# 10_-_FTDI.net
KiCad netlist of a schematic drawn in Altium Designer
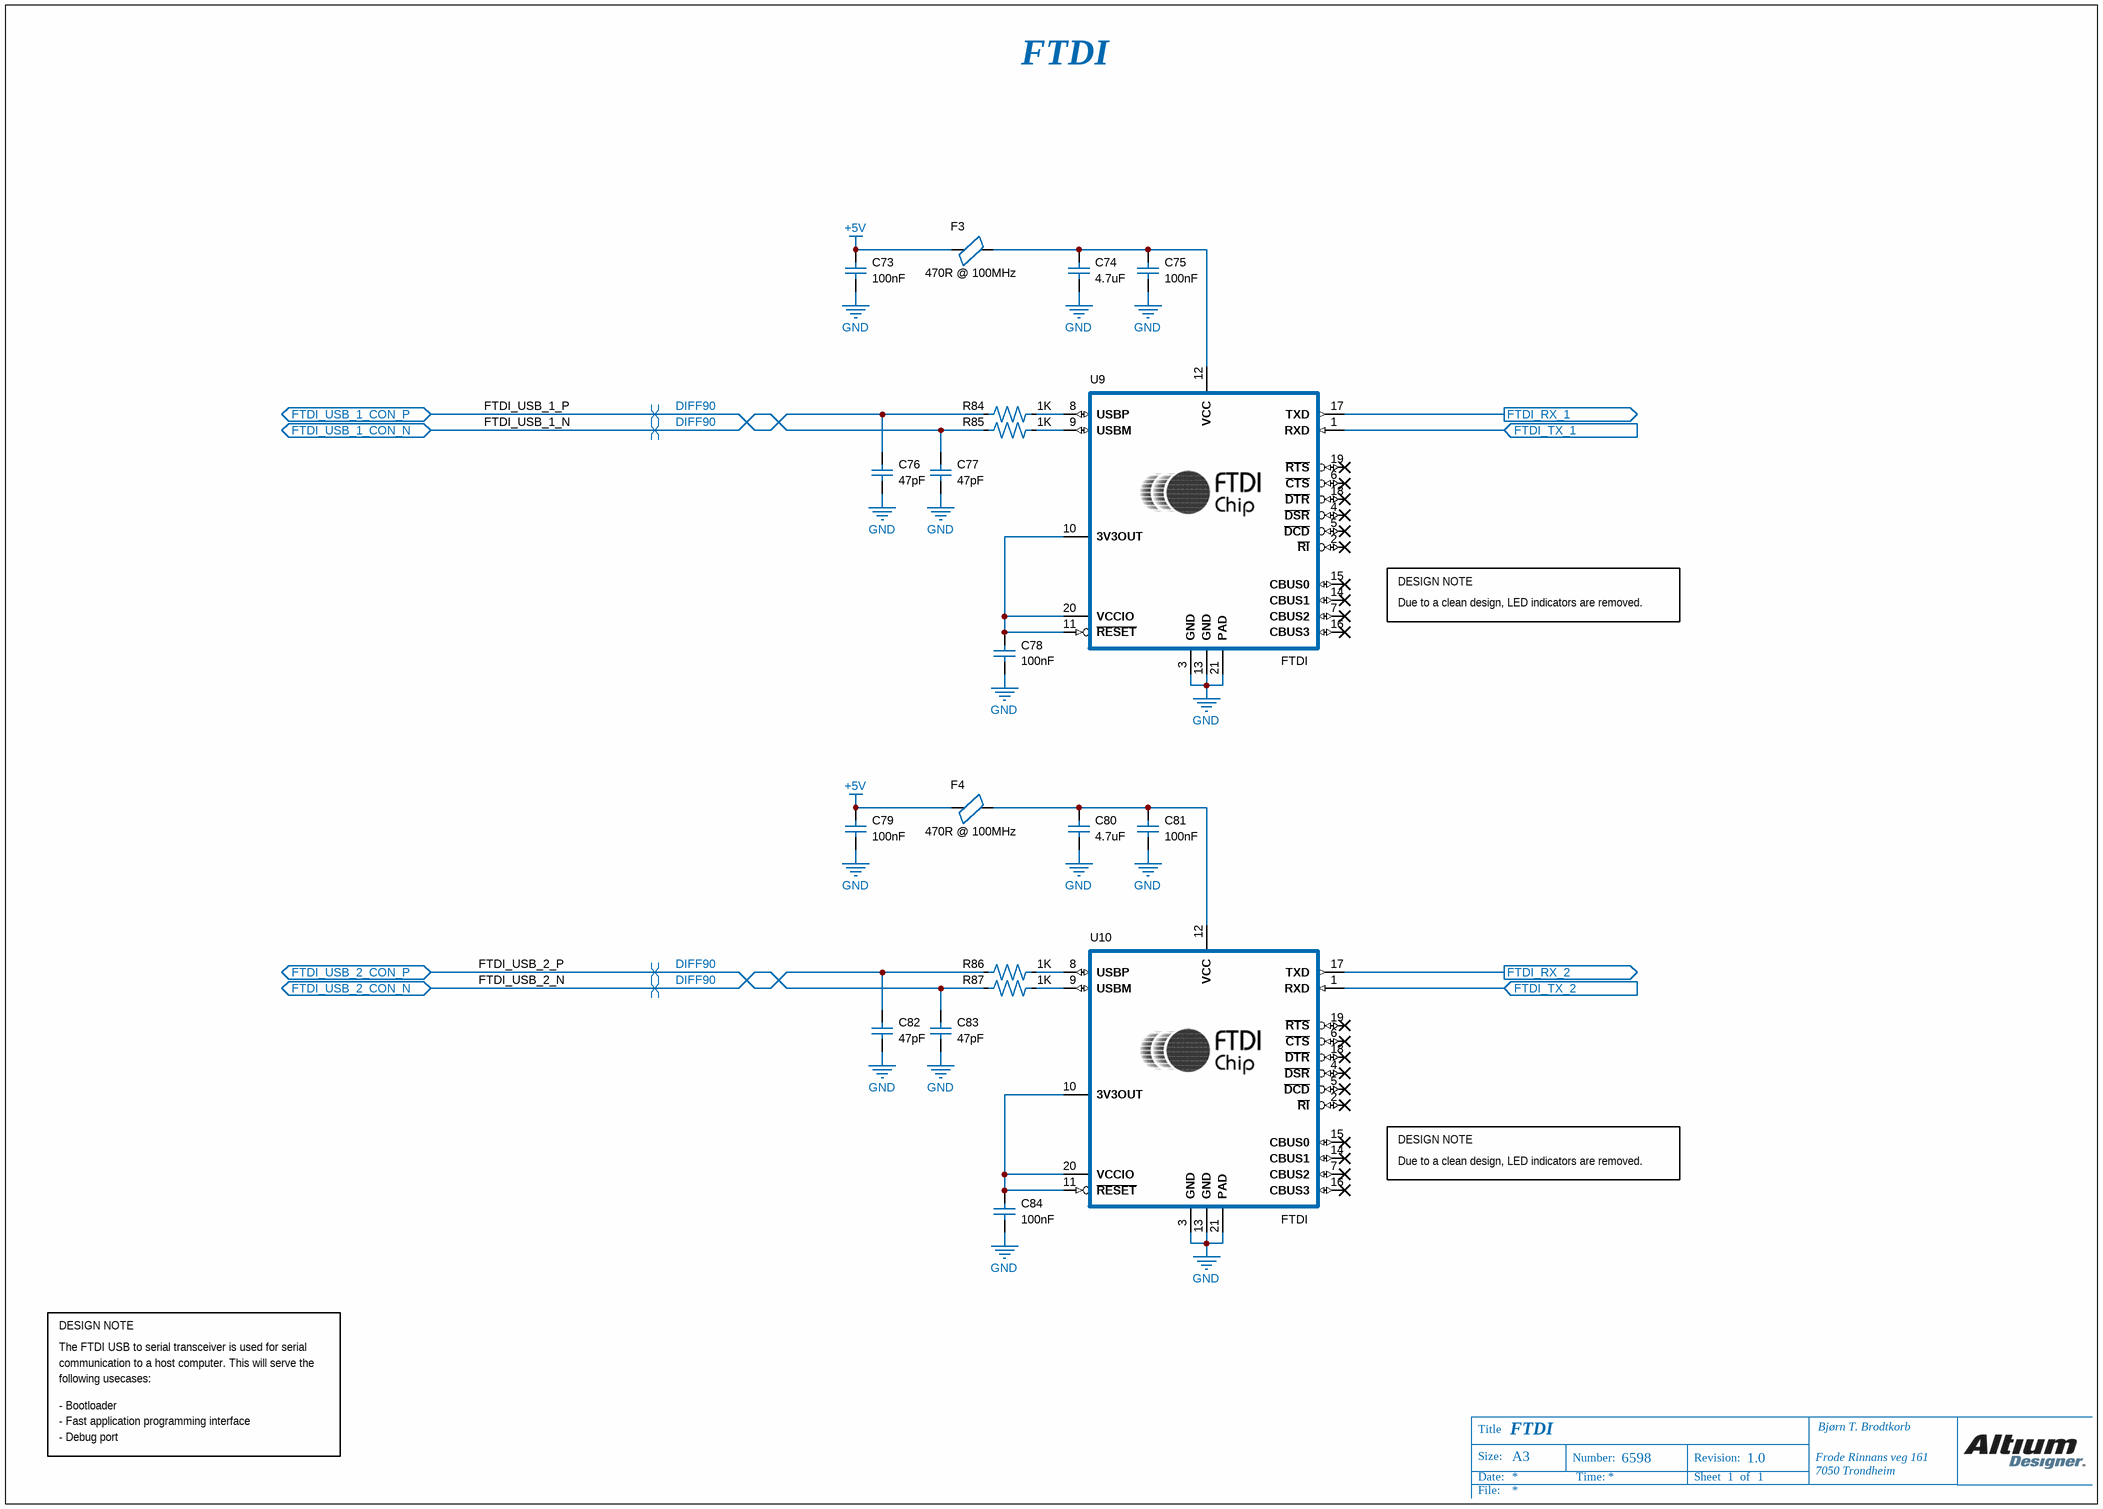
[diagram p0: [10] - FTDI.SchDoc]

(export (version "E")
  (design (tool "Eeschema 10.0.6"))
  (components
    (comp (ref "C73")
      (value "100nF")
      (footprint "C0402")
      (description "C0402")
      (fields (field (name "Comment") "04023C103KAT2A"))
      (libsource (lib "Passive components") (part "04023C103KAT2A"))
    )
    (comp (ref "C74")
      (value "4.7uF")
      (footprint "C0603")
      (description "C0603")
      (fields (field (name "Comment") "02016D104KAT2A"))
      (libsource (lib "Passive components") (part "02016D104KAT2A"))
    )
    (comp (ref "C75")
      (value "100nF")
      (footprint "C0402")
      (description "C0402")
      (fields (field (name "Comment") "04023C103KAT2A"))
      (libsource (lib "Passive components") (part "04023C103KAT2A"))
    )
    (comp (ref "C76")
      (value "47pF")
      (footprint "C0402")
      (description "C0402")
      (fields (field (name "Comment") "04023C103KAT2A"))
      (libsource (lib "Passive components") (part "04023C103KAT2A"))
    )
    (comp (ref "C77")
      (value "47pF")
      (footprint "C0402")
      (description "C0402")
      (fields (field (name "Comment") "04023C103KAT2A"))
      (libsource (lib "Passive components") (part "04023C103KAT2A"))
    )
    (comp (ref "C78")
      (value "100nF")
      (footprint "C0402")
      (description "C0402")
      (fields (field (name "Comment") "04023C103KAT2A"))
      (libsource (lib "Passive components") (part "04023C103KAT2A"))
    )
    (comp (ref "C79")
      (value "100nF")
      (footprint "C0402")
      (description "C0402")
      (fields (field (name "Comment") "04023C103KAT2A"))
      (libsource (lib "Passive components") (part "04023C103KAT2A"))
    )
    (comp (ref "C80")
      (value "4.7uF")
      (footprint "C0603")
      (description "C0603")
      (fields (field (name "Comment") "02016D104KAT2A"))
      (libsource (lib "Passive components") (part "02016D104KAT2A"))
    )
    (comp (ref "C81")
      (value "100nF")
      (footprint "C0402")
      (description "C0402")
      (fields (field (name "Comment") "04023C103KAT2A"))
      (libsource (lib "Passive components") (part "04023C103KAT2A"))
    )
    (comp (ref "C82")
      (value "47pF")
      (footprint "C0402")
      (description "C0402")
      (fields (field (name "Comment") "04023C103KAT2A"))
      (libsource (lib "Passive components") (part "04023C103KAT2A"))
    )
    (comp (ref "C83")
      (value "47pF")
      (footprint "C0402")
      (description "C0402")
      (fields (field (name "Comment") "04023C103KAT2A"))
      (libsource (lib "Passive components") (part "04023C103KAT2A"))
    )
    (comp (ref "C84")
      (value "100nF")
      (footprint "C0402")
      (description "C0402")
      (fields (field (name "Comment") "04023C103KAT2A"))
      (libsource (lib "Passive components") (part "04023C103KAT2A"))
    )
    (comp (ref "F3")
      (value "470R @ 100MHz")
      (footprint "Ferrite bead 0402")
      (description "Ferrite bead 0402")
      (fields (field (name "Comment") "BLM15AG102SN1D"))
      (libsource (lib "Passive components") (part "BLM15AG102SN1D"))
    )
    (comp (ref "F4")
      (value "470R @ 100MHz")
      (footprint "Ferrite bead 0402")
      (description "Ferrite bead 0402")
      (fields (field (name "Comment") "BLM15AG102SN1D"))
      (libsource (lib "Passive components") (part "BLM15AG102SN1D"))
    )
    (comp (ref "R84")
      (value "1K")
      (footprint "R0402")
      (description "R0402")
      (fields (field (name "Comment") "CRCW04020000Z0ED"))
      (libsource (lib "Passive components") (part "CRCW04020000Z0ED"))
    )
    (comp (ref "R85")
      (value "1K")
      (footprint "R0402")
      (description "R0402")
      (fields (field (name "Comment") "CRCW04020000Z0ED"))
      (libsource (lib "Passive components") (part "CRCW04020000Z0ED"))
    )
    (comp (ref "R86")
      (value "1K")
      (footprint "R0402")
      (description "R0402")
      (fields (field (name "Comment") "CRCW04020000Z0ED"))
      (libsource (lib "Passive components") (part "CRCW04020000Z0ED"))
    )
    (comp (ref "R87")
      (value "1K")
      (footprint "R0402")
      (description "R0402")
      (fields (field (name "Comment") "CRCW04020000Z0ED"))
      (libsource (lib "Passive components") (part "CRCW04020000Z0ED"))
    )
    (comp (ref "U9")
      (value "FTDI")
      (footprint "FT231XQ-R")
      (description "USB to RS-232 converter")
      (libsource (lib "IC") (part "FT231XQ-R"))
    )
    (comp (ref "U10")
      (value "FTDI")
      (footprint "FT231XQ-R")
      (description "USB to RS-232 converter")
      (libsource (lib "IC") (part "FT231XQ-R"))
    )
  )
  (nets
    (net (code "1") (name "+5V") (class "Default")
      (node (ref "C73") (pin "1") (pinfunction "1_1") (pintype "passive"))
      (node (ref "C79") (pin "1") (pinfunction "1_1") (pintype "passive"))
      (node (ref "F3") (pin "1") (pinfunction "1_1") (pintype "passive"))
      (node (ref "F4") (pin "1") (pinfunction "1_1") (pintype "passive"))
    )
    (net (code "2") (name "/FTDI_RX_1") (class "Default")
      (node (ref "U9") (pin "17") (pinfunction "TXD_17") (pintype "output"))
    )
    (net (code "3") (name "/FTDI_RX_2") (class "Default")
      (node (ref "U10") (pin "17") (pinfunction "TXD_17") (pintype "output"))
    )
    (net (code "4") (name "/FTDI_TX_1") (class "Default")
      (node (ref "U9") (pin "1") (pinfunction "RXD_1") (pintype "input"))
    )
    (net (code "5") (name "/FTDI_TX_2") (class "Default")
      (node (ref "U10") (pin "1") (pinfunction "RXD_1") (pintype "input"))
    )
    (net (code "6") (name "/FTDI_USB_1_N") (class "Default")
      (node (ref "C77") (pin "1") (pinfunction "1_1") (pintype "passive"))
      (node (ref "R85") (pin "1") (pinfunction "1_1") (pintype "passive"))
    )
    (net (code "7") (name "/FTDI_USB_1_P") (class "Default")
      (node (ref "C76") (pin "1") (pinfunction "1_1") (pintype "passive"))
      (node (ref "R84") (pin "1") (pinfunction "1_1") (pintype "passive"))
    )
    (net (code "8") (name "/FTDI_USB_2_N") (class "Default")
      (node (ref "C83") (pin "1") (pinfunction "1_1") (pintype "passive"))
      (node (ref "R87") (pin "1") (pinfunction "1_1") (pintype "passive"))
    )
    (net (code "9") (name "/FTDI_USB_2_P") (class "Default")
      (node (ref "C82") (pin "1") (pinfunction "1_1") (pintype "passive"))
      (node (ref "R86") (pin "1") (pinfunction "1_1") (pintype "passive"))
    )
    (net (code "10") (name "GND") (class "Default")
      (node (ref "C73") (pin "2") (pinfunction "2_2") (pintype "passive"))
      (node (ref "C74") (pin "2") (pinfunction "2_2") (pintype "passive"))
      (node (ref "C75") (pin "2") (pinfunction "2_2") (pintype "passive"))
      (node (ref "C76") (pin "2") (pinfunction "2_2") (pintype "passive"))
      (node (ref "C77") (pin "2") (pinfunction "2_2") (pintype "passive"))
      (node (ref "C78") (pin "2") (pinfunction "2_2") (pintype "passive"))
      (node (ref "C79") (pin "2") (pinfunction "2_2") (pintype "passive"))
      (node (ref "C80") (pin "2") (pinfunction "2_2") (pintype "passive"))
      (node (ref "C81") (pin "2") (pinfunction "2_2") (pintype "passive"))
      (node (ref "C82") (pin "2") (pinfunction "2_2") (pintype "passive"))
      (node (ref "C83") (pin "2") (pinfunction "2_2") (pintype "passive"))
      (node (ref "C84") (pin "2") (pinfunction "2_2") (pintype "passive"))
      (node (ref "U10") (pin "13") (pinfunction "GND_13") (pintype "power_in"))
      (node (ref "U10") (pin "21") (pinfunction "PAD_21") (pintype "power_in"))
      (node (ref "U10") (pin "3") (pinfunction "GND_3") (pintype "power_in"))
      (node (ref "U9") (pin "13") (pinfunction "GND_13") (pintype "power_in"))
      (node (ref "U9") (pin "21") (pinfunction "PAD_21") (pintype "power_in"))
      (node (ref "U9") (pin "3") (pinfunction "GND_3") (pintype "power_in"))
    )
    (net (code "11") (name "Net-(R84-3)") (class "Default")
      (node (ref "R84") (pin "2") (pinfunction "3_2") (pintype "passive"))
      (node (ref "U9") (pin "8") (pinfunction "USBP_8") (pintype "bidirectional"))
    )
    (net (code "12") (name "Net-(R85-3)") (class "Default")
      (node (ref "R85") (pin "2") (pinfunction "3_2") (pintype "passive"))
      (node (ref "U9") (pin "9") (pinfunction "USBM_9") (pintype "bidirectional"))
    )
    (net (code "13") (name "Net-(R86-3)") (class "Default")
      (node (ref "R86") (pin "2") (pinfunction "3_2") (pintype "passive"))
      (node (ref "U10") (pin "8") (pinfunction "USBP_8") (pintype "bidirectional"))
    )
    (net (code "14") (name "Net-(R87-3)") (class "Default")
      (node (ref "R87") (pin "2") (pinfunction "3_2") (pintype "passive"))
      (node (ref "U10") (pin "9") (pinfunction "USBM_9") (pintype "bidirectional"))
    )
    (net (code "15") (name "Net-(U9-3V3OUT)") (class "Default")
      (node (ref "C78") (pin "1") (pinfunction "1_1") (pintype "passive"))
      (node (ref "U9") (pin "10") (pinfunction "3V3OUT_10") (pintype "power_in"))
      (node (ref "U9") (pin "11") (pinfunction "~{RESET}_11") (pintype "input"))
      (node (ref "U9") (pin "20") (pinfunction "VCCIO_20") (pintype "power_in"))
    )
    (net (code "16") (name "Net-(U9-VCC)") (class "Default")
      (node (ref "C74") (pin "1") (pinfunction "1_1") (pintype "passive"))
      (node (ref "C75") (pin "1") (pinfunction "1_1") (pintype "passive"))
      (node (ref "F3") (pin "2") (pinfunction "2_2") (pintype "passive"))
      (node (ref "U9") (pin "12") (pinfunction "VCC_12") (pintype "power_in"))
    )
    (net (code "17") (name "Net-(U10-3V3OUT)") (class "Default")
      (node (ref "C84") (pin "1") (pinfunction "1_1") (pintype "passive"))
      (node (ref "U10") (pin "10") (pinfunction "3V3OUT_10") (pintype "power_in"))
      (node (ref "U10") (pin "11") (pinfunction "~{RESET}_11") (pintype "input"))
      (node (ref "U10") (pin "20") (pinfunction "VCCIO_20") (pintype "power_in"))
    )
    (net (code "18") (name "Net-(U10-VCC)") (class "Default")
      (node (ref "C80") (pin "1") (pinfunction "1_1") (pintype "passive"))
      (node (ref "C81") (pin "1") (pinfunction "1_1") (pintype "passive"))
      (node (ref "F4") (pin "2") (pinfunction "2_2") (pintype "passive"))
      (node (ref "U10") (pin "12") (pinfunction "VCC_12") (pintype "power_in"))
    )
    (net (code "19") (name "unconnected-(U9-CBUS0-Pad15)") (class "Default")
      (node (ref "U9") (pin "15") (pinfunction "CBUS0_15") (pintype "bidirectional+no_connect"))
    )
    (net (code "20") (name "unconnected-(U9-CBUS1-Pad14)") (class "Default")
      (node (ref "U9") (pin "14") (pinfunction "CBUS1_14") (pintype "bidirectional+no_connect"))
    )
    (net (code "21") (name "unconnected-(U9-CBUS2-Pad7)") (class "Default")
      (node (ref "U9") (pin "7") (pinfunction "CBUS2_7") (pintype "bidirectional+no_connect"))
    )
    (net (code "22") (name "unconnected-(U9-CBUS3-Pad16)") (class "Default")
      (node (ref "U9") (pin "16") (pinfunction "CBUS3_16") (pintype "bidirectional+no_connect"))
    )
    (net (code "23") (name "unconnected-(U9-~{CTS}-Pad6)") (class "Default")
      (node (ref "U9") (pin "6") (pinfunction "~{CTS}_6") (pintype "bidirectional+no_connect"))
    )
    (net (code "24") (name "unconnected-(U9-~{DCD}-Pad5)") (class "Default")
      (node (ref "U9") (pin "5") (pinfunction "~{DCD}_5") (pintype "bidirectional+no_connect"))
    )
    (net (code "25") (name "unconnected-(U9-~{DSR}-Pad4)") (class "Default")
      (node (ref "U9") (pin "4") (pinfunction "~{DSR}_4") (pintype "bidirectional+no_connect"))
    )
    (net (code "26") (name "unconnected-(U9-~{DTR}-Pad18)") (class "Default")
      (node (ref "U9") (pin "18") (pinfunction "~{DTR}_18") (pintype "bidirectional+no_connect"))
    )
    (net (code "27") (name "unconnected-(U9-~{RI}-Pad2)") (class "Default")
      (node (ref "U9") (pin "2") (pinfunction "~{RI}_2") (pintype "bidirectional+no_connect"))
    )
    (net (code "28") (name "unconnected-(U9-~{RTS}-Pad19)") (class "Default")
      (node (ref "U9") (pin "19") (pinfunction "~{RTS}_19") (pintype "bidirectional+no_connect"))
    )
    (net (code "29") (name "unconnected-(U10-CBUS0-Pad15)") (class "Default")
      (node (ref "U10") (pin "15") (pinfunction "CBUS0_15") (pintype "bidirectional+no_connect"))
    )
    (net (code "30") (name "unconnected-(U10-CBUS1-Pad14)") (class "Default")
      (node (ref "U10") (pin "14") (pinfunction "CBUS1_14") (pintype "bidirectional+no_connect"))
    )
    (net (code "31") (name "unconnected-(U10-CBUS2-Pad7)") (class "Default")
      (node (ref "U10") (pin "7") (pinfunction "CBUS2_7") (pintype "bidirectional+no_connect"))
    )
    (net (code "32") (name "unconnected-(U10-CBUS3-Pad16)") (class "Default")
      (node (ref "U10") (pin "16") (pinfunction "CBUS3_16") (pintype "bidirectional+no_connect"))
    )
    (net (code "33") (name "unconnected-(U10-~{CTS}-Pad6)") (class "Default")
      (node (ref "U10") (pin "6") (pinfunction "~{CTS}_6") (pintype "bidirectional+no_connect"))
    )
    (net (code "34") (name "unconnected-(U10-~{DCD}-Pad5)") (class "Default")
      (node (ref "U10") (pin "5") (pinfunction "~{DCD}_5") (pintype "bidirectional+no_connect"))
    )
    (net (code "35") (name "unconnected-(U10-~{DSR}-Pad4)") (class "Default")
      (node (ref "U10") (pin "4") (pinfunction "~{DSR}_4") (pintype "bidirectional+no_connect"))
    )
    (net (code "36") (name "unconnected-(U10-~{DTR}-Pad18)") (class "Default")
      (node (ref "U10") (pin "18") (pinfunction "~{DTR}_18") (pintype "bidirectional+no_connect"))
    )
    (net (code "37") (name "unconnected-(U10-~{RI}-Pad2)") (class "Default")
      (node (ref "U10") (pin "2") (pinfunction "~{RI}_2") (pintype "bidirectional+no_connect"))
    )
    (net (code "38") (name "unconnected-(U10-~{RTS}-Pad19)") (class "Default")
      (node (ref "U10") (pin "19") (pinfunction "~{RTS}_19") (pintype "bidirectional+no_connect"))
    )
  )
)
